# Zotino.net
KiCad netlist of a schematic drawn in Altium Designer
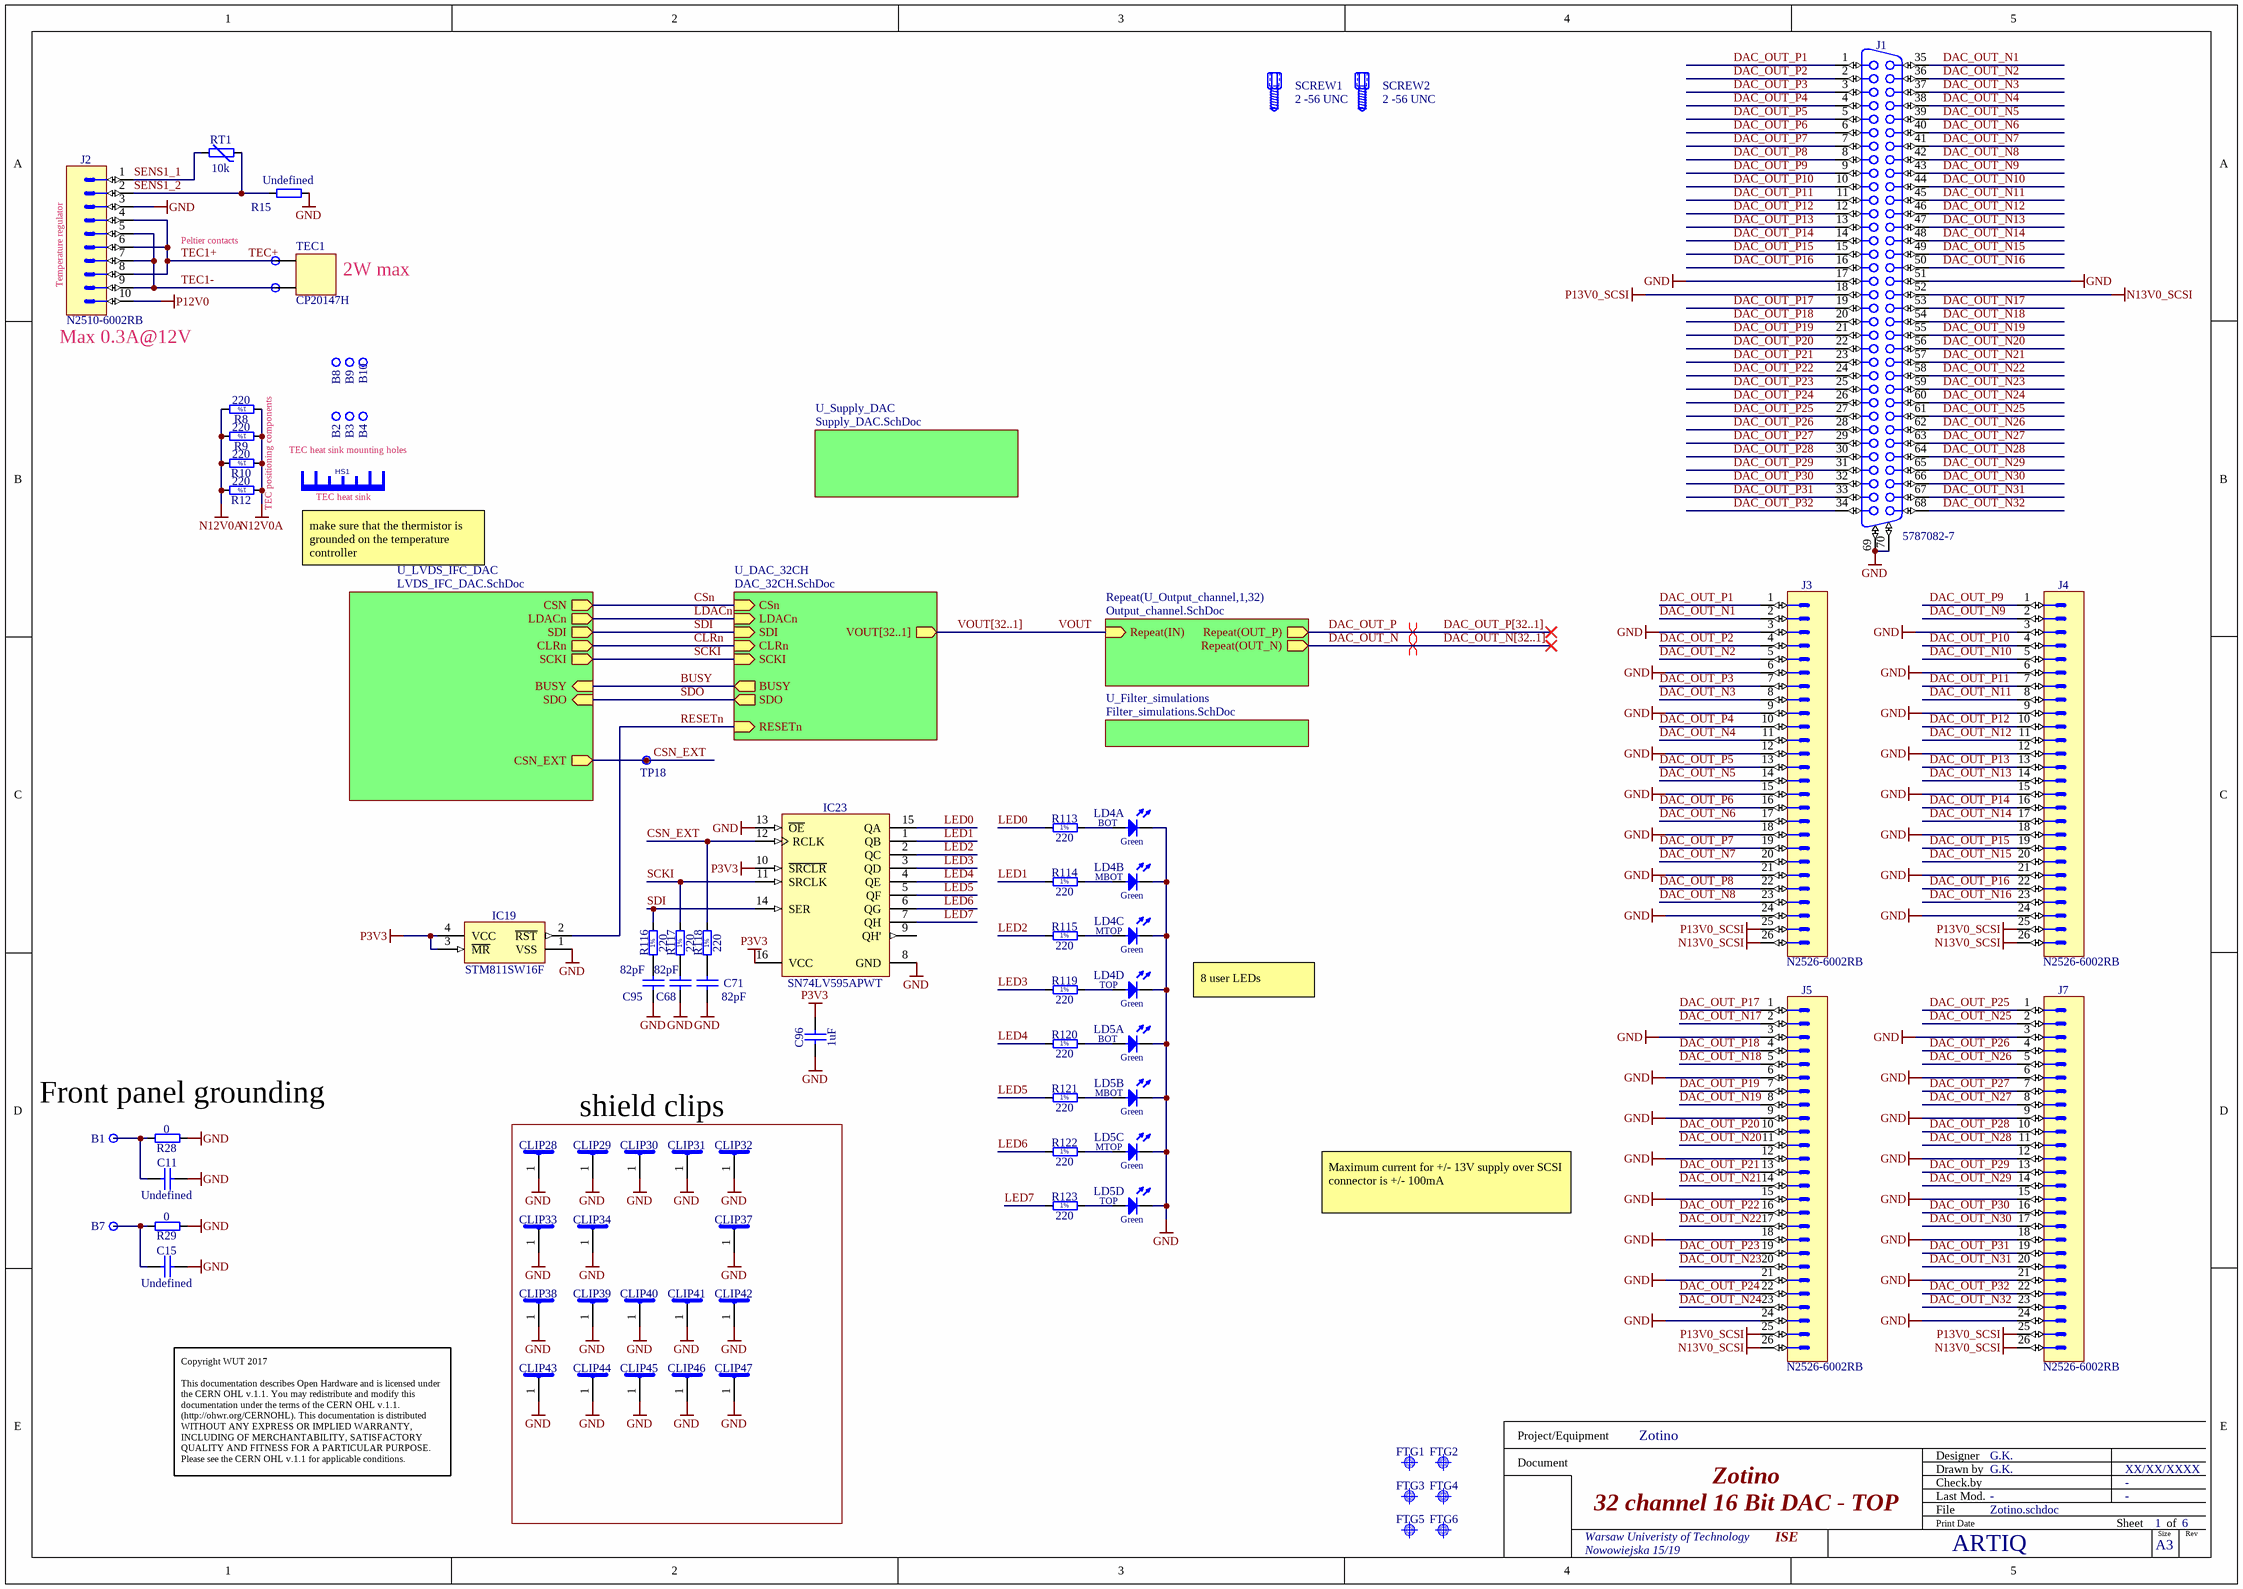
[diagram p0: Zotino.schdoc]

(export (version "E")
  (design (tool "Eeschema 10.0.6"))
  (components
    (comp (ref "B1")
      (value "Plated Hole")
      (footprint "MTG270_500")
      (description "Single Terminal Socket")
      (fields (field (name "PART NUMBER") "PLATED_HOLE2.7_PAD5.0") (field (name "AUTHOR") "CERN DEM JMW"))
      (libsource (lib "Eletro-mechanical") (part "Single Terminal Socket"))
    )
    (comp (ref "B2")
      (value "Plated Hole")
      (footprint "c130h80")
      (description "Single Terminal Socket")
      (fields (field (name "PART NUMBER") "PLATED_HOLE0.8_PAD1.3") (field (name "AUTHOR") "CERN DEM JLC"))
      (libsource (lib "Eletro-mechanical") (part "Single Terminal Socket"))
    )
    (comp (ref "B3")
      (value "Plated Hole")
      (footprint "c130h80")
      (description "Single Terminal Socket")
      (fields (field (name "PART NUMBER") "PLATED_HOLE0.8_PAD1.3") (field (name "AUTHOR") "CERN DEM JLC"))
      (libsource (lib "Eletro-mechanical") (part "Single Terminal Socket"))
    )
    (comp (ref "B4")
      (value "Plated Hole")
      (footprint "c130h80")
      (description "Single Terminal Socket")
      (fields (field (name "PART NUMBER") "PLATED_HOLE0.8_PAD1.3") (field (name "AUTHOR") "CERN DEM JLC"))
      (libsource (lib "Eletro-mechanical") (part "Single Terminal Socket"))
    )
    (comp (ref "B5")
      (value "Plated Hole")
      (footprint "c160h110")
      (description "Single Terminal Socket")
      (fields (field (name "PART NUMBER") "PLATED_HOLE1.1_PAD1.6") (field (name "AUTHOR") "CERN DEM JLC"))
      (libsource (lib "Eletro-mechanical") (part "Single Terminal Socket"))
    )
    (comp (ref "B6")
      (value "Plated Hole")
      (footprint "c160h110")
      (description "Single Terminal Socket")
      (fields (field (name "PART NUMBER") "PLATED_HOLE1.1_PAD1.6") (field (name "AUTHOR") "CERN DEM JLC"))
      (libsource (lib "Eletro-mechanical") (part "Single Terminal Socket"))
    )
    (comp (ref "B7")
      (value "Plated Hole")
      (footprint "MTG270_500")
      (description "Single Terminal Socket")
      (fields (field (name "PART NUMBER") "PLATED_HOLE2.7_PAD5.0") (field (name "AUTHOR") "CERN DEM JMW"))
      (libsource (lib "Eletro-mechanical") (part "Single Terminal Socket"))
    )
    (comp (ref "B8")
      (value "Plated Hole")
      (footprint "c130h80")
      (description "Single Terminal Socket")
      (fields (field (name "PART NUMBER") "PLATED_HOLE0.8_PAD1.3") (field (name "AUTHOR") "CERN DEM JLC"))
      (libsource (lib "Eletro-mechanical") (part "Single Terminal Socket"))
    )
    (comp (ref "B9")
      (value "Plated Hole")
      (footprint "c130h80")
      (description "Single Terminal Socket")
      (fields (field (name "PART NUMBER") "PLATED_HOLE0.8_PAD1.3") (field (name "AUTHOR") "CERN DEM JLC"))
      (libsource (lib "Eletro-mechanical") (part "Single Terminal Socket"))
    )
    (comp (ref "B10")
      (value "Plated Hole")
      (footprint "c130h80")
      (description "Single Terminal Socket")
      (fields (field (name "PART NUMBER") "PLATED_HOLE0.8_PAD1.3") (field (name "AUTHOR") "CERN DEM JLC"))
      (libsource (lib "Eletro-mechanical") (part "Single Terminal Socket"))
    )
    (comp (ref "C11")
      (value "Undefined")
      (footprint "CAPC2012X135N")
      (description "Non-polarised capacitor")
      (fields (field (name "PART NUMBER") "CC0805_NO-VALUE") (field (name "AUTHOR") "CERN DEM JLC"))
      (libsource (lib "Capacitors") (part "Capacitor - non polarized"))
    )
    (comp (ref "C15")
      (value "Undefined")
      (footprint "CAPC2012X135N")
      (description "Non-polarised capacitor")
      (fields (field (name "PART NUMBER") "CC0805_NO-VALUE") (field (name "AUTHOR") "CERN DEM JLC"))
      (libsource (lib "Capacitors") (part "Capacitor - non polarized"))
    )
    (comp (ref "C68")
      (value "82pF")
      (footprint "CAPC1608X87N")
      (description "Non-polarised capacitor")
      (fields
        (field (name "PART NUMBER") "CC0603_82PF_50V_5%_NP0")
        (field (name "VOLTAGE") "50V")
        (field (name "AUTHOR") "CERN DEM JLC")
      )
      (libsource (lib "Capacitors") (part "Capacitor - non polarized"))
    )
    (comp (ref "C71")
      (value "82pF")
      (footprint "CAPC1608X87N")
      (description "Non-polarised capacitor")
      (fields
        (field (name "PART NUMBER") "CC0603_82PF_50V_5%_NP0")
        (field (name "VOLTAGE") "50V")
        (field (name "AUTHOR") "CERN DEM JLC")
      )
      (libsource (lib "Capacitors") (part "Capacitor - non polarized"))
    )
    (comp (ref "C95")
      (value "82pF")
      (footprint "CAPC1608X87N")
      (description "Non-polarised capacitor")
      (fields
        (field (name "PART NUMBER") "CC0603_82PF_50V_5%_NP0")
        (field (name "VOLTAGE") "50V")
        (field (name "AUTHOR") "CERN DEM JLC")
      )
      (libsource (lib "Capacitors") (part "Capacitor - non polarized"))
    )
    (comp (ref "C96")
      (value "1uF")
      (footprint "CAPC1608X87N")
      (description "Non-polarised capacitor")
      (fields
        (field (name "PART NUMBER") "CC0603_1UF_25V_10%_X7R")
        (field (name "VOLTAGE") "25V")
        (field (name "AUTHOR") "CERN DEM JLC")
      )
      (libsource (lib "Capacitors") (part "Capacitor - non polarized"))
    )
    (comp (ref "CLIP28")
      (value "S1411-46R")
      (footprint "CLIP_HOLLAND-SHIELDING_LC")
      (description "Surface Mount Clip for PCB Screening Covers")
      (fields (field (name "MANUFACTURER") "HARWIN") (field (name "AUTHOR") "CERN DEM JLC"))
      (libsource (lib "LIBRARY_SCH") (part "SHIELD_CLIP"))
    )
    (comp (ref "CLIP29")
      (value "S1411-46R")
      (footprint "CLIP_HOLLAND-SHIELDING_LC")
      (description "Surface Mount Clip for PCB Screening Covers")
      (fields (field (name "MANUFACTURER") "HARWIN") (field (name "AUTHOR") "CERN DEM JLC"))
      (libsource (lib "LIBRARY_SCH") (part "SHIELD_CLIP"))
    )
    (comp (ref "CLIP30")
      (value "S1411-46R")
      (footprint "CLIP_HOLLAND-SHIELDING_LC")
      (description "Surface Mount Clip for PCB Screening Covers")
      (fields (field (name "MANUFACTURER") "HARWIN") (field (name "AUTHOR") "CERN DEM JLC"))
      (libsource (lib "LIBRARY_SCH") (part "SHIELD_CLIP"))
    )
    (comp (ref "CLIP31")
      (value "S1411-46R")
      (footprint "CLIP_HOLLAND-SHIELDING_LC")
      (description "Surface Mount Clip for PCB Screening Covers")
      (fields (field (name "MANUFACTURER") "HARWIN") (field (name "AUTHOR") "CERN DEM JLC"))
      (libsource (lib "LIBRARY_SCH") (part "SHIELD_CLIP"))
    )
    (comp (ref "CLIP32")
      (value "S1411-46R")
      (footprint "CLIP_HOLLAND-SHIELDING_LC")
      (description "Surface Mount Clip for PCB Screening Covers")
      (fields (field (name "MANUFACTURER") "HARWIN") (field (name "AUTHOR") "CERN DEM JLC"))
      (libsource (lib "LIBRARY_SCH") (part "SHIELD_CLIP"))
    )
    (comp (ref "CLIP33")
      (value "S1411-46R")
      (footprint "CLIP_HOLLAND-SHIELDING_LC")
      (description "Surface Mount Clip for PCB Screening Covers")
      (fields (field (name "MANUFACTURER") "HARWIN") (field (name "AUTHOR") "CERN DEM JLC"))
      (libsource (lib "LIBRARY_SCH") (part "SHIELD_CLIP"))
    )
    (comp (ref "CLIP34")
      (value "S1411-46R")
      (footprint "CLIP_HOLLAND-SHIELDING_LC")
      (description "Surface Mount Clip for PCB Screening Covers")
      (fields (field (name "MANUFACTURER") "HARWIN") (field (name "AUTHOR") "CERN DEM JLC"))
      (libsource (lib "LIBRARY_SCH") (part "SHIELD_CLIP"))
    )
    (comp (ref "CLIP37")
      (value "S1411-46R")
      (footprint "CLIP_HOLLAND-SHIELDING_LC")
      (description "Surface Mount Clip for PCB Screening Covers")
      (fields (field (name "MANUFACTURER") "HARWIN") (field (name "AUTHOR") "CERN DEM JLC"))
      (libsource (lib "LIBRARY_SCH") (part "SHIELD_CLIP"))
    )
    (comp (ref "CLIP38")
      (value "S1411-46R")
      (footprint "CLIP_HOLLAND-SHIELDING_LC")
      (description "Surface Mount Clip for PCB Screening Covers")
      (fields (field (name "MANUFACTURER") "HARWIN") (field (name "AUTHOR") "CERN DEM JLC"))
      (libsource (lib "LIBRARY_SCH") (part "SHIELD_CLIP"))
    )
    (comp (ref "CLIP39")
      (value "S1411-46R")
      (footprint "CLIP_HOLLAND-SHIELDING_LC")
      (description "Surface Mount Clip for PCB Screening Covers")
      (fields (field (name "MANUFACTURER") "HARWIN") (field (name "AUTHOR") "CERN DEM JLC"))
      (libsource (lib "LIBRARY_SCH") (part "SHIELD_CLIP"))
    )
    (comp (ref "CLIP40")
      (value "S1411-46R")
      (footprint "CLIP_HOLLAND-SHIELDING_LC")
      (description "Surface Mount Clip for PCB Screening Covers")
      (fields (field (name "MANUFACTURER") "HARWIN") (field (name "AUTHOR") "CERN DEM JLC"))
      (libsource (lib "LIBRARY_SCH") (part "SHIELD_CLIP"))
    )
    (comp (ref "CLIP41")
      (value "S1411-46R")
      (footprint "CLIP_HOLLAND-SHIELDING_LC")
      (description "Surface Mount Clip for PCB Screening Covers")
      (fields (field (name "MANUFACTURER") "HARWIN") (field (name "AUTHOR") "CERN DEM JLC"))
      (libsource (lib "LIBRARY_SCH") (part "SHIELD_CLIP"))
    )
    (comp (ref "CLIP42")
      (value "S1411-46R")
      (footprint "CLIP_HOLLAND-SHIELDING_LC")
      (description "Surface Mount Clip for PCB Screening Covers")
      (fields (field (name "MANUFACTURER") "HARWIN") (field (name "AUTHOR") "CERN DEM JLC"))
      (libsource (lib "LIBRARY_SCH") (part "SHIELD_CLIP"))
    )
    (comp (ref "CLIP43")
      (value "S1411-46R")
      (footprint "CLIP_HOLLAND-SHIELDING_LC")
      (description "Surface Mount Clip for PCB Screening Covers")
      (fields (field (name "MANUFACTURER") "HARWIN") (field (name "AUTHOR") "CERN DEM JLC"))
      (libsource (lib "LIBRARY_SCH") (part "SHIELD_CLIP"))
    )
    (comp (ref "CLIP44")
      (value "S1411-46R")
      (footprint "CLIP_HOLLAND-SHIELDING_LC")
      (description "Surface Mount Clip for PCB Screening Covers")
      (fields (field (name "MANUFACTURER") "HARWIN") (field (name "AUTHOR") "CERN DEM JLC"))
      (libsource (lib "LIBRARY_SCH") (part "SHIELD_CLIP"))
    )
    (comp (ref "CLIP45")
      (value "S1411-46R")
      (footprint "CLIP_HOLLAND-SHIELDING_LC")
      (description "Surface Mount Clip for PCB Screening Covers")
      (fields (field (name "MANUFACTURER") "HARWIN") (field (name "AUTHOR") "CERN DEM JLC"))
      (libsource (lib "LIBRARY_SCH") (part "SHIELD_CLIP"))
    )
    (comp (ref "CLIP46")
      (value "S1411-46R")
      (footprint "CLIP_HOLLAND-SHIELDING_LC")
      (description "Surface Mount Clip for PCB Screening Covers")
      (fields (field (name "MANUFACTURER") "HARWIN") (field (name "AUTHOR") "CERN DEM JLC"))
      (libsource (lib "LIBRARY_SCH") (part "SHIELD_CLIP"))
    )
    (comp (ref "CLIP47")
      (value "S1411-46R")
      (footprint "CLIP_HOLLAND-SHIELDING_LC")
      (description "Surface Mount Clip for PCB Screening Covers")
      (fields (field (name "MANUFACTURER") "HARWIN") (field (name "AUTHOR") "CERN DEM JLC"))
      (libsource (lib "LIBRARY_SCH") (part "SHIELD_CLIP"))
    )
    (comp (ref "FTG1")
      (value "Use only in PCB")
      (footprint "FIDUCIAL_TOP_C100-200")
      (description "Fiducial Target")
      (fields (field (name "PART NUMBER") "FIDUCIAL_TARGET_C100-200") (field (name "AUTHOR") "CERN DEM JLC"))
      (libsource (lib "Eletro-mechanical") (part "Fiducial Target"))
    )
    (comp (ref "FTG2")
      (value "Use only in PCB")
      (footprint "FIDUCIAL_TOP_C100-200")
      (description "Fiducial Target")
      (fields (field (name "PART NUMBER") "FIDUCIAL_TARGET_C100-200") (field (name "AUTHOR") "CERN DEM JLC"))
      (libsource (lib "Eletro-mechanical") (part "Fiducial Target"))
    )
    (comp (ref "FTG3")
      (value "Use only in PCB")
      (footprint "FIDUCIAL_TOP_S100-200")
      (description "Fiducial Target")
      (fields (field (name "PART NUMBER") "FIDUCIAL_TARGET_S100-200") (field (name "AUTHOR") "CERN DEM JLC"))
      (libsource (lib "Eletro-mechanical") (part "Fiducial Target"))
    )
    (comp (ref "FTG4")
      (value "Use only in PCB")
      (footprint "FIDUCIAL_TOP_S100-200")
      (description "Fiducial Target")
      (fields (field (name "PART NUMBER") "FIDUCIAL_TARGET_S100-200") (field (name "AUTHOR") "CERN DEM JLC"))
      (libsource (lib "Eletro-mechanical") (part "Fiducial Target"))
    )
    (comp (ref "FTG5")
      (value "Use only in PCB")
      (footprint "FIDUCIAL_TOP_S100-200")
      (description "Fiducial Target")
      (fields (field (name "PART NUMBER") "FIDUCIAL_TARGET_S100-200") (field (name "AUTHOR") "CERN DEM JLC"))
      (libsource (lib "Eletro-mechanical") (part "Fiducial Target"))
    )
    (comp (ref "FTG6")
      (value "Use only in PCB")
      (footprint "FIDUCIAL_TOP_S100-200")
      (description "Fiducial Target")
      (fields (field (name "PART NUMBER") "FIDUCIAL_TARGET_S100-200") (field (name "AUTHOR") "CERN DEM JLC"))
      (libsource (lib "Eletro-mechanical") (part "Fiducial Target"))
    )
    (comp (ref "HS1")
      (value "Heat Sink No Pad")
      (footprint "HSINK_ATS_ATS-56001-C3-R0")
      (description "Heat Sink Without Pad")
      (fields
        (field (name "PART NUMBER") "HSINK_ATS_ATS-56001-C3-R0")
        (field (name "MANUFACTURER") "ADVENCED THERMAL SOLUTION (ATS)")
        (field (name "AUTHOR") "GK")
      )
      (libsource (lib "LIBRARY_SCH") (part "HEAT_SINK_19x19x9"))
    )
    (comp (ref "IC19")
      (value "STM811SW16F")
      (footprint "SOT143N")
      (description "Microprocessor Reset Circuit")
      (fields (field (name "MANUFACTURER") "ST MICROELECTRONICS") (field (name "AUTHOR") "CERN DEM JLC"))
      (libsource (lib "ICs And Semiconductors") (part "STM811"))
    )
    (comp (ref "IC23")
      (value "SN74LV595APWT")
      (footprint "SOP65P640X120-16N")
      (description "8-Bit Shift Register With 3-State Output Register")
      (fields (field (name "MANUFACTURER") "TEXAS INSTRUMENTS") (field (name "AUTHOR") "CERN DEM JLC"))
      (libsource (lib "ICs And Semiconductors") (part "74595"))
    )
    (comp (ref "J1")
      (value "D-SUB")
      (footprint "TYCO_5787082-7")
      (description "68 contacts, AMPLIMITE .050\", Right Angled Receptacle Series III")
      (fields
        (field (name "PART NUMBER") "TYCO_5787082-7")
        (field (name "MANUFACTURER") "TYCO ELECTRONICS")
        (field (name "MANUFACTURER PART NUMBER") "5787082-7")
        (field (name "AUTHOR") "CERN DEM JLC")
      )
      (libsource (lib "Connectors") (part "TYCO_5787082-7"))
    )
    (comp (ref "J2")
      (value "Header 10")
      (footprint "3M_N2510-6002RB")
      (description "Connector 10 Male")
      (fields
        (field (name "PART NUMBER") "3M_N2510-6002RB")
        (field (name "MANUFACTURER") "3M")
        (field (name "MANUFACTURER PART NUMBER") "N2510-6002RB")
        (field (name "AUTHOR") "CERN DEM JLC")
      )
      (libsource (lib "Connectors") (part "Connector 10 Male"))
    )
    (comp (ref "J3")
      (value "Header 26")
      (footprint "3M_N2526-6002RB")
      (description "Connector 26 Male")
      (fields
        (field (name "PART NUMBER") "3M_N2526-6002RB")
        (field (name "MANUFACTURER") "3M")
        (field (name "MANUFACTURER PART NUMBER") "N2526-6002RB")
        (field (name "AUTHOR") "CERN DEM JLC")
      )
      (libsource (lib "Connectors") (part "Connector 26 Male"))
    )
    (comp (ref "J4")
      (value "Header 26")
      (footprint "3M_N2526-6002RB")
      (description "Connector 26 Male")
      (fields
        (field (name "PART NUMBER") "3M_N2526-6002RB")
        (field (name "MANUFACTURER") "3M")
        (field (name "MANUFACTURER PART NUMBER") "N2526-6002RB")
        (field (name "AUTHOR") "CERN DEM JLC")
      )
      (libsource (lib "Connectors") (part "Connector 26 Male"))
    )
    (comp (ref "J5")
      (value "Header 26")
      (footprint "3M_N2526-6002RB")
      (description "Connector 26 Male")
      (fields
        (field (name "PART NUMBER") "3M_N2526-6002RB")
        (field (name "MANUFACTURER") "3M")
        (field (name "MANUFACTURER PART NUMBER") "N2526-6002RB")
        (field (name "AUTHOR") "CERN DEM JLC")
      )
      (libsource (lib "Connectors") (part "Connector 26 Male"))
    )
    (comp (ref "J7")
      (value "Header 26")
      (footprint "3M_N2526-6002RB")
      (description "Connector 26 Male")
      (fields
        (field (name "PART NUMBER") "3M_N2526-6002RB")
        (field (name "MANUFACTURER") "3M")
        (field (name "MANUFACTURER PART NUMBER") "N2526-6002RB")
        (field (name "AUTHOR") "CERN DEM JLC")
      )
      (libsource (lib "Connectors") (part "Connector 26 Male"))
    )
    (comp (ref "LD4")
      (value "Green")
      (footprint "LED_BIVAR_H485CGDL")
      (description "LED x4 Green 1C2A-BOT_3C4A_5C6A_7C8A-TOP")
      (fields
        (field (name "PART NUMBER") "LED_BIVAR_H485CGDL")
        (field (name "MANUFACTURER") "BIVAR")
        (field (name "AUTHOR") "CERN DEM JLC")
      )
      (libsource (lib "ICs And Semiconductors") (part "LED x4 Green 1C2A-BOT_3C4A_5C6A_7C8A-TOP"))
    )
    (comp (ref "LD5")
      (value "Green")
      (footprint "LED_BIVAR_H485CGDL")
      (description "LED x4 Green 1C2A-BOT_3C4A_5C6A_7C8A-TOP")
      (fields
        (field (name "PART NUMBER") "LED_BIVAR_H485CGDL")
        (field (name "MANUFACTURER") "BIVAR")
        (field (name "AUTHOR") "CERN DEM JLC")
      )
      (libsource (lib "ICs And Semiconductors") (part "LED x4 Green 1C2A-BOT_3C4A_5C6A_7C8A-TOP"))
    )
    (comp (ref "R8")
      (value "220")
      (footprint "RESC1608X55N")
      (description "Resistor - 1%")
      (fields
        (field (name "PART NUMBER") "R0603_220R_1%_0.1W_100PPM")
        (field (name "POWER") "0.1W")
        (field (name "AUTHOR") "CERN DEM JLC")
      )
      (libsource (lib "Resistors") (part "Resistor - 1%"))
    )
    (comp (ref "R9")
      (value "220")
      (footprint "RESC1608X55N")
      (description "Resistor - 1%")
      (fields
        (field (name "PART NUMBER") "R0603_220R_1%_0.1W_100PPM")
        (field (name "POWER") "0.1W")
        (field (name "AUTHOR") "CERN DEM JLC")
      )
      (libsource (lib "Resistors") (part "Resistor - 1%"))
    )
    (comp (ref "R10")
      (value "220")
      (footprint "RESC1608X55N")
      (description "Resistor - 1%")
      (fields
        (field (name "PART NUMBER") "R0603_220R_1%_0.1W_100PPM")
        (field (name "POWER") "0.1W")
        (field (name "AUTHOR") "CERN DEM JLC")
      )
      (libsource (lib "Resistors") (part "Resistor - 1%"))
    )
    (comp (ref "R12")
      (value "220")
      (footprint "RESC1608X55N")
      (description "Resistor - 1%")
      (fields
        (field (name "PART NUMBER") "R0603_220R_1%_0.1W_100PPM")
        (field (name "POWER") "0.1W")
        (field (name "AUTHOR") "CERN DEM JLC")
      )
      (libsource (lib "Resistors") (part "Resistor - 1%"))
    )
    (comp (ref "R15")
      (value "Undefined")
      (footprint "RESC1608X55N")
      (description "Resistor")
      (fields (field (name "PART NUMBER") "R0603_NO-VALUE") (field (name "AUTHOR") "CERN DEM JLC"))
      (libsource (lib "Resistors") (part "Resistor"))
    )
    (comp (ref "R28")
      (value "0")
      (footprint "RESC1608X55N")
      (description "Resistor")
      (fields
        (field (name "PART NUMBER") "R0603_0R_JUMPER")
        (field (name "MANUFACTURER") "GENERIC")
        (field (name "AUTHOR") "CERN DEM JLC")
      )
      (libsource (lib "Resistors") (part "Resistor"))
    )
    (comp (ref "R29")
      (value "0")
      (footprint "RESC1608X55N")
      (description "Resistor")
      (fields
        (field (name "PART NUMBER") "R0603_0R_JUMPER")
        (field (name "MANUFACTURER") "GENERIC")
        (field (name "AUTHOR") "CERN DEM JLC")
      )
      (libsource (lib "Resistors") (part "Resistor"))
    )
    (comp (ref "R113")
      (value "220")
      (footprint "RESC1608X55N")
      (description "Resistor - 1%")
      (fields
        (field (name "PART NUMBER") "R0603_220R_1%_0.1W_100PPM")
        (field (name "POWER") "0.1W")
        (field (name "AUTHOR") "CERN DEM JLC")
      )
      (libsource (lib "Resistors") (part "Resistor - 1%"))
    )
    (comp (ref "R114")
      (value "220")
      (footprint "RESC1608X55N")
      (description "Resistor - 1%")
      (fields
        (field (name "PART NUMBER") "R0603_220R_1%_0.1W_100PPM")
        (field (name "POWER") "0.1W")
        (field (name "AUTHOR") "CERN DEM JLC")
      )
      (libsource (lib "Resistors") (part "Resistor - 1%"))
    )
    (comp (ref "R115")
      (value "220")
      (footprint "RESC1608X55N")
      (description "Resistor - 1%")
      (fields
        (field (name "PART NUMBER") "R0603_220R_1%_0.1W_100PPM")
        (field (name "POWER") "0.1W")
        (field (name "AUTHOR") "CERN DEM JLC")
      )
      (libsource (lib "Resistors") (part "Resistor - 1%"))
    )
    (comp (ref "R116")
      (value "220")
      (footprint "RESC1608X55N")
      (description "Resistor - 1%")
      (fields
        (field (name "PART NUMBER") "R0603_220R_1%_0.1W_100PPM")
        (field (name "POWER") "0.1W")
        (field (name "AUTHOR") "CERN DEM JLC")
      )
      (libsource (lib "Resistors") (part "Resistor - 1%"))
    )
    (comp (ref "R117")
      (value "220")
      (footprint "RESC1608X55N")
      (description "Resistor - 1%")
      (fields
        (field (name "PART NUMBER") "R0603_220R_1%_0.1W_100PPM")
        (field (name "POWER") "0.1W")
        (field (name "AUTHOR") "CERN DEM JLC")
      )
      (libsource (lib "Resistors") (part "Resistor - 1%"))
    )
    (comp (ref "R118")
      (value "220")
      (footprint "RESC1608X55N")
      (description "Resistor - 1%")
      (fields
        (field (name "PART NUMBER") "R0603_220R_1%_0.1W_100PPM")
        (field (name "POWER") "0.1W")
        (field (name "AUTHOR") "CERN DEM JLC")
      )
      (libsource (lib "Resistors") (part "Resistor - 1%"))
    )
    (comp (ref "R119")
      (value "220")
      (footprint "RESC1608X55N")
      (description "Resistor - 1%")
      (fields
        (field (name "PART NUMBER") "R0603_220R_1%_0.1W_100PPM")
        (field (name "POWER") "0.1W")
        (field (name "AUTHOR") "CERN DEM JLC")
      )
      (libsource (lib "Resistors") (part "Resistor - 1%"))
    )
    (comp (ref "R120")
      (value "220")
      (footprint "RESC1608X55N")
      (description "Resistor - 1%")
      (fields
        (field (name "PART NUMBER") "R0603_220R_1%_0.1W_100PPM")
        (field (name "POWER") "0.1W")
        (field (name "AUTHOR") "CERN DEM JLC")
      )
      (libsource (lib "Resistors") (part "Resistor - 1%"))
    )
    (comp (ref "R121")
      (value "220")
      (footprint "RESC1608X55N")
      (description "Resistor - 1%")
      (fields
        (field (name "PART NUMBER") "R0603_220R_1%_0.1W_100PPM")
        (field (name "POWER") "0.1W")
        (field (name "AUTHOR") "CERN DEM JLC")
      )
      (libsource (lib "Resistors") (part "Resistor - 1%"))
    )
    (comp (ref "R122")
      (value "220")
      (footprint "RESC1608X55N")
      (description "Resistor - 1%")
      (fields
        (field (name "PART NUMBER") "R0603_220R_1%_0.1W_100PPM")
        (field (name "POWER") "0.1W")
        (field (name "AUTHOR") "CERN DEM JLC")
      )
      (libsource (lib "Resistors") (part "Resistor - 1%"))
    )
    (comp (ref "R123")
      (value "220")
      (footprint "RESC1608X55N")
      (description "Resistor - 1%")
      (fields
        (field (name "PART NUMBER") "R0603_220R_1%_0.1W_100PPM")
        (field (name "POWER") "0.1W")
        (field (name "AUTHOR") "CERN DEM JLC")
      )
      (libsource (lib "Resistors") (part "Resistor - 1%"))
    )
    (comp (ref "RT1")
      (value "10k")
      (footprint "THERMC1608X90N")
      (description "Thermistor NTC (Negative Temperature Coefficient)")
      (fields
        (field (name "PART NUMBER") "THERM_NTC_10K_EPCOS_B57330V2103J260")
        (field (name "POWER") "180mW")
        (field (name "AUTHOR") "CERN DEM BC")
      )
      (libsource (lib "Resistors") (part "Thermistor NTC"))
    )
    (comp (ref "SCREW1")
      (value "2 -56 UNC")
      (footprint "TYCO_786585-2")
      (description "SCSI Screw Lock")
      (fields
        (field (name "PART NUMBER") "TYCO_786585-2")
        (field (name "MANUFACTURER") "TYCO ELECTRONICS")
        (field (name "AUTHOR") "GK")
      )
      (libsource (lib "LIBRARY_SCH") (part "MECH_Tyco_SCSI_Screwlock"))
    )
    (comp (ref "SCREW2")
      (value "2 -56 UNC")
      (footprint "TYCO_786585-2")
      (description "SCSI Screw Lock")
      (fields
        (field (name "PART NUMBER") "TYCO_786585-2")
        (field (name "MANUFACTURER") "TYCO ELECTRONICS")
        (field (name "AUTHOR") "GK")
      )
      (libsource (lib "LIBRARY_SCH") (part "MECH_Tyco_SCSI_Screwlock"))
    )
    (comp (ref "TEC1")
      (value "CP20147H")
      (footprint "TEC_CP20147H")
      (description "Peltier Module 15x15 mm")
      (libsource (lib "LIBRARY_SCH") (part "TEC_CP20147H"))
    )
    (comp (ref "TP18")
      (value "Test Point")
      (footprint "TPS127")
      (fields (field (name "PART NUMBER") "SMD_PAD_1.27X1.27MM") (field (name "AUTHOR") "CERN DEM JLC"))
      (libsource (lib "Eletro-mechanical") (part "Test Point"))
    )
  )
  (nets
    (net (code "35") (name "/CSN_EXT") (class "Default")
      (node (ref "IC23") (pin "12") (pinfunction "RCLK_12") (pintype "input"))
      (node (ref "R118") (pin "2") (pinfunction "2_2") (pintype "passive"))
      (node (ref "TP18") (pin "1") (pinfunction "1_1") (pintype "bidirectional"))
    )
    (net (code "38") (name "/DAC_OUT_N1") (class "Default")
      (node (ref "J1") (pin "35") (pinfunction "35_35") (pintype "bidirectional"))
      (node (ref "J3") (pin "2") (pinfunction "2_2") (pintype "bidirectional"))
    )
    (net (code "39") (name "/DAC_OUT_N2") (class "Default")
      (node (ref "J1") (pin "36") (pinfunction "36_36") (pintype "bidirectional"))
      (node (ref "J3") (pin "5") (pinfunction "5_5") (pintype "bidirectional"))
    )
    (net (code "40") (name "/DAC_OUT_N3") (class "Default")
      (node (ref "J1") (pin "37") (pinfunction "37_37") (pintype "bidirectional"))
      (node (ref "J3") (pin "8") (pinfunction "8_8") (pintype "bidirectional"))
    )
    (net (code "41") (name "/DAC_OUT_N4") (class "Default")
      (node (ref "J1") (pin "38") (pinfunction "38_38") (pintype "bidirectional"))
      (node (ref "J3") (pin "11") (pinfunction "11_11") (pintype "bidirectional"))
    )
    (net (code "42") (name "/DAC_OUT_N5") (class "Default")
      (node (ref "J1") (pin "39") (pinfunction "39_39") (pintype "bidirectional"))
      (node (ref "J3") (pin "14") (pinfunction "14_14") (pintype "bidirectional"))
    )
    (net (code "43") (name "/DAC_OUT_N6") (class "Default")
      (node (ref "J1") (pin "40") (pinfunction "40_40") (pintype "bidirectional"))
      (node (ref "J3") (pin "17") (pinfunction "17_17") (pintype "bidirectional"))
    )
    (net (code "44") (name "/DAC_OUT_N7") (class "Default")
      (node (ref "J1") (pin "41") (pinfunction "41_41") (pintype "bidirectional"))
      (node (ref "J3") (pin "20") (pinfunction "20_20") (pintype "bidirectional"))
    )
    (net (code "45") (name "/DAC_OUT_N8") (class "Default")
      (node (ref "J1") (pin "42") (pinfunction "42_42") (pintype "bidirectional"))
      (node (ref "J3") (pin "23") (pinfunction "23_23") (pintype "bidirectional"))
    )
    (net (code "46") (name "/DAC_OUT_N9") (class "Default")
      (node (ref "J1") (pin "43") (pinfunction "43_43") (pintype "bidirectional"))
      (node (ref "J4") (pin "2") (pinfunction "2_2") (pintype "bidirectional"))
    )
    (net (code "47") (name "/DAC_OUT_N10") (class "Default")
      (node (ref "J1") (pin "44") (pinfunction "44_44") (pintype "bidirectional"))
      (node (ref "J4") (pin "5") (pinfunction "5_5") (pintype "bidirectional"))
    )
    (net (code "48") (name "/DAC_OUT_N11") (class "Default")
      (node (ref "J1") (pin "45") (pinfunction "45_45") (pintype "bidirectional"))
      (node (ref "J4") (pin "8") (pinfunction "8_8") (pintype "bidirectional"))
    )
    (net (code "49") (name "/DAC_OUT_N12") (class "Default")
      (node (ref "J1") (pin "46") (pinfunction "46_46") (pintype "bidirectional"))
      (node (ref "J4") (pin "11") (pinfunction "11_11") (pintype "bidirectional"))
    )
    (net (code "50") (name "/DAC_OUT_N13") (class "Default")
      (node (ref "J1") (pin "47") (pinfunction "47_47") (pintype "bidirectional"))
      (node (ref "J4") (pin "14") (pinfunction "14_14") (pintype "bidirectional"))
    )
    (net (code "51") (name "/DAC_OUT_N14") (class "Default")
      (node (ref "J1") (pin "48") (pinfunction "48_48") (pintype "bidirectional"))
      (node (ref "J4") (pin "17") (pinfunction "17_17") (pintype "bidirectional"))
    )
    (net (code "52") (name "/DAC_OUT_N15") (class "Default")
      (node (ref "J1") (pin "49") (pinfunction "49_49") (pintype "bidirectional"))
      (node (ref "J4") (pin "20") (pinfunction "20_20") (pintype "bidirectional"))
    )
    (net (code "53") (name "/DAC_OUT_N16") (class "Default")
      (node (ref "J1") (pin "50") (pinfunction "50_50") (pintype "bidirectional"))
      (node (ref "J4") (pin "23") (pinfunction "23_23") (pintype "bidirectional"))
    )
    (net (code "54") (name "/DAC_OUT_N17") (class "Default")
      (node (ref "J1") (pin "53") (pinfunction "53_53") (pintype "bidirectional"))
      (node (ref "J5") (pin "2") (pinfunction "2_2") (pintype "bidirectional"))
    )
    (net (code "55") (name "/DAC_OUT_N18") (class "Default")
      (node (ref "J1") (pin "54") (pinfunction "54_54") (pintype "bidirectional"))
      (node (ref "J5") (pin "5") (pinfunction "5_5") (pintype "bidirectional"))
    )
    (net (code "56") (name "/DAC_OUT_N19") (class "Default")
      (node (ref "J1") (pin "55") (pinfunction "55_55") (pintype "bidirectional"))
      (node (ref "J5") (pin "8") (pinfunction "8_8") (pintype "bidirectional"))
    )
    (net (code "57") (name "/DAC_OUT_N20") (class "Default")
      (node (ref "J1") (pin "56") (pinfunction "56_56") (pintype "bidirectional"))
      (node (ref "J5") (pin "11") (pinfunction "11_11") (pintype "bidirectional"))
    )
    (net (code "58") (name "/DAC_OUT_N21") (class "Default")
      (node (ref "J1") (pin "57") (pinfunction "57_57") (pintype "bidirectional"))
      (node (ref "J5") (pin "14") (pinfunction "14_14") (pintype "bidirectional"))
    )
    (net (code "59") (name "/DAC_OUT_N22") (class "Default")
      (node (ref "J1") (pin "58") (pinfunction "58_58") (pintype "bidirectional"))
      (node (ref "J5") (pin "17") (pinfunction "17_17") (pintype "bidirectional"))
    )
    (net (code "60") (name "/DAC_OUT_N23") (class "Default")
      (node (ref "J1") (pin "59") (pinfunction "59_59") (pintype "bidirectional"))
      (node (ref "J5") (pin "20") (pinfunction "20_20") (pintype "bidirectional"))
    )
    (net (code "61") (name "/DAC_OUT_N24") (class "Default")
      (node (ref "J1") (pin "60") (pinfunction "60_60") (pintype "bidirectional"))
      (node (ref "J5") (pin "23") (pinfunction "23_23") (pintype "bidirectional"))
    )
    (net (code "62") (name "/DAC_OUT_N25") (class "Default")
      (node (ref "J1") (pin "61") (pinfunction "61_61") (pintype "bidirectional"))
      (node (ref "J7") (pin "2") (pinfunction "2_2") (pintype "bidirectional"))
    )
    (net (code "63") (name "/DAC_OUT_N26") (class "Default")
      (node (ref "J1") (pin "62") (pinfunction "62_62") (pintype "bidirectional"))
      (node (ref "J7") (pin "5") (pinfunction "5_5") (pintype "bidirectional"))
    )
    (net (code "64") (name "/DAC_OUT_N27") (class "Default")
      (node (ref "J1") (pin "63") (pinfunction "63_63") (pintype "bidirectional"))
      (node (ref "J7") (pin "8") (pinfunction "8_8") (pintype "bidirectional"))
    )
    (net (code "65") (name "/DAC_OUT_N28") (class "Default")
      (node (ref "J1") (pin "64") (pinfunction "64_64") (pintype "bidirectional"))
      (node (ref "J7") (pin "11") (pinfunction "11_11") (pintype "bidirectional"))
    )
    (net (code "66") (name "/DAC_OUT_N29") (class "Default")
      (node (ref "J1") (pin "65") (pinfunction "65_65") (pintype "bidirectional"))
      (node (ref "J7") (pin "14") (pinfunction "14_14") (pintype "bidirectional"))
    )
    (net (code "67") (name "/DAC_OUT_N30") (class "Default")
      (node (ref "J1") (pin "66") (pinfunction "66_66") (pintype "bidirectional"))
      (node (ref "J7") (pin "17") (pinfunction "17_17") (pintype "bidirectional"))
    )
    (net (code "68") (name "/DAC_OUT_N31") (class "Default")
      (node (ref "J1") (pin "67") (pinfunction "67_67") (pintype "bidirectional"))
      (node (ref "J7") (pin "20") (pinfunction "20_20") (pintype "bidirectional"))
    )
    (net (code "69") (name "/DAC_OUT_N32") (class "Default")
      (node (ref "J1") (pin "68") (pinfunction "68_68") (pintype "bidirectional"))
      (node (ref "J7") (pin "23") (pinfunction "23_23") (pintype "bidirectional"))
    )
    (net (code "72") (name "/DAC_OUT_P1") (class "Default")
      (node (ref "J1") (pin "1") (pinfunction "1_1") (pintype "bidirectional"))
      (node (ref "J3") (pin "1") (pinfunction "1_1") (pintype "bidirectional"))
    )
    (net (code "73") (name "/DAC_OUT_P2") (class "Default")
      (node (ref "J1") (pin "2") (pinfunction "2_2") (pintype "bidirectional"))
      (node (ref "J3") (pin "4") (pinfunction "4_4") (pintype "bidirectional"))
    )
    (net (code "74") (name "/DAC_OUT_P3") (class "Default")
      (node (ref "J1") (pin "3") (pinfunction "3_3") (pintype "bidirectional"))
      (node (ref "J3") (pin "7") (pinfunction "7_7") (pintype "bidirectional"))
    )
    (net (code "75") (name "/DAC_OUT_P4") (class "Default")
      (node (ref "J1") (pin "4") (pinfunction "4_4") (pintype "bidirectional"))
      (node (ref "J3") (pin "10") (pinfunction "10_10") (pintype "bidirectional"))
    )
    (net (code "76") (name "/DAC_OUT_P5") (class "Default")
      (node (ref "J1") (pin "5") (pinfunction "5_5") (pintype "bidirectional"))
      (node (ref "J3") (pin "13") (pinfunction "13_13") (pintype "bidirectional"))
    )
    (net (code "77") (name "/DAC_OUT_P6") (class "Default")
      (node (ref "J1") (pin "6") (pinfunction "6_6") (pintype "bidirectional"))
      (node (ref "J3") (pin "16") (pinfunction "16_16") (pintype "bidirectional"))
    )
    (net (code "78") (name "/DAC_OUT_P7") (class "Default")
      (node (ref "J1") (pin "7") (pinfunction "7_7") (pintype "bidirectional"))
      (node (ref "J3") (pin "19") (pinfunction "19_19") (pintype "bidirectional"))
    )
    (net (code "79") (name "/DAC_OUT_P8") (class "Default")
      (node (ref "J1") (pin "8") (pinfunction "8_8") (pintype "bidirectional"))
      (node (ref "J3") (pin "22") (pinfunction "22_22") (pintype "bidirectional"))
    )
    (net (code "80") (name "/DAC_OUT_P9") (class "Default")
      (node (ref "J1") (pin "9") (pinfunction "9_9") (pintype "bidirectional"))
      (node (ref "J4") (pin "1") (pinfunction "1_1") (pintype "bidirectional"))
    )
    (net (code "81") (name "/DAC_OUT_P10") (class "Default")
      (node (ref "J1") (pin "10") (pinfunction "10_10") (pintype "bidirectional"))
      (node (ref "J4") (pin "4") (pinfunction "4_4") (pintype "bidirectional"))
    )
    (net (code "82") (name "/DAC_OUT_P11") (class "Default")
      (node (ref "J1") (pin "11") (pinfunction "11_11") (pintype "bidirectional"))
      (node (ref "J4") (pin "7") (pinfunction "7_7") (pintype "bidirectional"))
    )
    (net (code "83") (name "/DAC_OUT_P12") (class "Default")
      (node (ref "J1") (pin "12") (pinfunction "12_12") (pintype "bidirectional"))
      (node (ref "J4") (pin "10") (pinfunction "10_10") (pintype "bidirectional"))
    )
    (net (code "84") (name "/DAC_OUT_P13") (class "Default")
      (node (ref "J1") (pin "13") (pinfunction "13_13") (pintype "bidirectional"))
      (node (ref "J4") (pin "13") (pinfunction "13_13") (pintype "bidirectional"))
    )
    (net (code "85") (name "/DAC_OUT_P14") (class "Default")
      (node (ref "J1") (pin "14") (pinfunction "14_14") (pintype "bidirectional"))
      (node (ref "J4") (pin "16") (pinfunction "16_16") (pintype "bidirectional"))
    )
    (net (code "86") (name "/DAC_OUT_P15") (class "Default")
      (node (ref "J1") (pin "15") (pinfunction "15_15") (pintype "bidirectional"))
      (node (ref "J4") (pin "19") (pinfunction "19_19") (pintype "bidirectional"))
    )
    (net (code "87") (name "/DAC_OUT_P16") (class "Default")
      (node (ref "J1") (pin "16") (pinfunction "16_16") (pintype "bidirectional"))
      (node (ref "J4") (pin "22") (pinfunction "22_22") (pintype "bidirectional"))
    )
    (net (code "88") (name "/DAC_OUT_P17") (class "Default")
      (node (ref "J1") (pin "19") (pinfunction "19_19") (pintype "bidirectional"))
      (node (ref "J5") (pin "1") (pinfunction "1_1") (pintype "bidirectional"))
    )
    (net (code "89") (name "/DAC_OUT_P18") (class "Default")
      (node (ref "J1") (pin "20") (pinfunction "20_20") (pintype "bidirectional"))
      (node (ref "J5") (pin "4") (pinfunction "4_4") (pintype "bidirectional"))
    )
    (net (code "90") (name "/DAC_OUT_P19") (class "Default")
      (node (ref "J1") (pin "21") (pinfunction "21_21") (pintype "bidirectional"))
      (node (ref "J5") (pin "7") (pinfunction "7_7") (pintype "bidirectional"))
    )
    (net (code "91") (name "/DAC_OUT_P20") (class "Default")
      (node (ref "J1") (pin "22") (pinfunction "22_22") (pintype "bidirectional"))
      (node (ref "J5") (pin "10") (pinfunction "10_10") (pintype "bidirectional"))
    )
    (net (code "92") (name "/DAC_OUT_P21") (class "Default")
      (node (ref "J1") (pin "23") (pinfunction "23_23") (pintype "bidirectional"))
      (node (ref "J5") (pin "13") (pinfunction "13_13") (pintype "bidirectional"))
    )
    (net (code "93") (name "/DAC_OUT_P22") (class "Default")
      (node (ref "J1") (pin "24") (pinfunction "24_24") (pintype "bidirectional"))
      (node (ref "J5") (pin "16") (pinfunction "16_16") (pintype "bidirectional"))
    )
    (net (code "94") (name "/DAC_OUT_P23") (class "Default")
      (node (ref "J1") (pin "25") (pinfunction "25_25") (pintype "bidirectional"))
      (node (ref "J5") (pin "19") (pinfunction "19_19") (pintype "bidirectional"))
    )
    (net (code "95") (name "/DAC_OUT_P24") (class "Default")
      (node (ref "J1") (pin "26") (pinfunction "26_26") (pintype "bidirectional"))
      (node (ref "J5") (pin "22") (pinfunction "22_22") (pintype "bidirectional"))
    )
    (net (code "96") (name "/DAC_OUT_P25") (class "Default")
      (node (ref "J1") (pin "27") (pinfunction "27_27") (pintype "bidirectional"))
      (node (ref "J7") (pin "1") (pinfunction "1_1") (pintype "bidirectional"))
    )
    (net (code "97") (name "/DAC_OUT_P26") (class "Default")
      (node (ref "J1") (pin "28") (pinfunction "28_28") (pintype "bidirectional"))
      (node (ref "J7") (pin "4") (pinfunction "4_4") (pintype "bidirectional"))
    )
    (net (code "98") (name "/DAC_OUT_P27") (class "Default")
      (node (ref "J1") (pin "29") (pinfunction "29_29") (pintype "bidirectional"))
      (node (ref "J7") (pin "7") (pinfunction "7_7") (pintype "bidirectional"))
    )
    (net (code "99") (name "/DAC_OUT_P28") (class "Default")
      (node (ref "J1") (pin "30") (pinfunction "30_30") (pintype "bidirectional"))
      (node (ref "J7") (pin "10") (pinfunction "10_10") (pintype "bidirectional"))
    )
    (net (code "100") (name "/DAC_OUT_P29") (class "Default")
      (node (ref "J1") (pin "31") (pinfunction "31_31") (pintype "bidirectional"))
      (node (ref "J7") (pin "13") (pinfunction "13_13") (pintype "bidirectional"))
    )
    (net (code "101") (name "/DAC_OUT_P30") (class "Default")
      (node (ref "J1") (pin "32") (pinfunction "32_32") (pintype "bidirectional"))
      (node (ref "J7") (pin "16") (pinfunction "16_16") (pintype "bidirectional"))
    )
    (net (code "102") (name "/DAC_OUT_P31") (class "Default")
      (node (ref "J1") (pin "33") (pinfunction "33_33") (pintype "bidirectional"))
      (node (ref "J7") (pin "19") (pinfunction "19_19") (pintype "bidirectional"))
    )
    (net (code "103") (name "/DAC_OUT_P32") (class "Default")
      (node (ref "J1") (pin "34") (pinfunction "34_34") (pintype "bidirectional"))
      (node (ref "J7") (pin "22") (pinfunction "22_22") (pintype "bidirectional"))
    )
    (net (code "106") (name "/LED0") (class "Default")
      (node (ref "IC23") (pin "15") (pinfunction "QA_15") (pintype "tri_state"))
      (node (ref "R113") (pin "1") (pinfunction "1_1") (pintype "passive"))
    )
    (net (code "107") (name "/LED1") (class "Default")
      (node (ref "IC23") (pin "1") (pinfunction "QB_1") (pintype "tri_state"))
      (node (ref "R114") (pin "1") (pinfunction "1_1") (pintype "passive"))
    )
    (net (code "108") (name "/LED2") (class "Default")
      (node (ref "IC23") (pin "2") (pinfunction "QC_2") (pintype "tri_state"))
      (node (ref "R115") (pin "1") (pinfunction "1_1") (pintype "passive"))
    )
    (net (code "109") (name "/LED3") (class "Default")
      (node (ref "IC23") (pin "3") (pinfunction "QD_3") (pintype "tri_state"))
      (node (ref "R119") (pin "1") (pinfunction "1_1") (pintype "passive"))
    )
    (net (code "110") (name "/LED4") (class "Default")
      (node (ref "IC23") (pin "4") (pinfunction "QE_4") (pintype "tri_state"))
      (node (ref "R120") (pin "1") (pinfunction "1_1") (pintype "passive"))
    )
    (net (code "111") (name "/LED5") (class "Default")
      (node (ref "IC23") (pin "5") (pinfunction "QF_5") (pintype "tri_state"))
      (node (ref "R121") (pin "1") (pinfunction "1_1") (pintype "passive"))
    )
    (net (code "112") (name "/LED6") (class "Default")
      (node (ref "IC23") (pin "6") (pinfunction "QG_6") (pintype "tri_state"))
      (node (ref "R122") (pin "1") (pinfunction "1_1") (pintype "passive"))
    )
    (net (code "113") (name "/LED7") (class "Default")
      (node (ref "IC23") (pin "7") (pinfunction "QH_7") (pintype "tri_state"))
      (node (ref "R123") (pin "1") (pinfunction "1_1") (pintype "passive"))
    )
    (net (code "114") (name "/RESETn") (class "Default")
      (node (ref "IC19") (pin "2") (pinfunction "~{RST}_2") (pintype "output"))
    )
    (net (code "115") (name "/SCKI") (class "Default")
      (node (ref "IC23") (pin "11") (pinfunction "SRCLK_11") (pintype "input"))
      (node (ref "R117") (pin "2") (pinfunction "2_2") (pintype "passive"))
    )
    (net (code "116") (name "/SDI") (class "Default")
      (node (ref "IC23") (pin "14") (pinfunction "SER_14") (pintype "input"))
      (node (ref "R116") (pin "2") (pinfunction "2_2") (pintype "passive"))
    )
    (net (code "118") (name "/SENS1_1") (class "Default")
      (node (ref "J2") (pin "1") (pinfunction "1_1") (pintype "bidirectional"))
      (node (ref "RT1") (pin "1") (pinfunction "1_1") (pintype "passive"))
    )
    (net (code "119") (name "/SENS1_2") (class "Default")
      (node (ref "J2") (pin "2") (pinfunction "2_2") (pintype "bidirectional"))
      (node (ref "R15") (pin "2") (pinfunction "2_2") (pintype "passive"))
      (node (ref "RT1") (pin "2") (pinfunction "2_2") (pintype "passive"))
    )
    (net (code "120") (name "/TEC+") (class "Default")
      (node (ref "B5") (pin "1") (pinfunction "1_1") (pintype "bidirectional"))
      (node (ref "J2") (pin "4") (pinfunction "4_4") (pintype "bidirectional"))
      (node (ref "J2") (pin "6") (pinfunction "6_6") (pintype "bidirectional"))
      (node (ref "J2") (pin "8") (pinfunction "8_8") (pintype "bidirectional"))
    )
    (net (code "121") (name "/TEC1-") (class "Default")
      (node (ref "B6") (pin "1") (pinfunction "1_1") (pintype "bidirectional"))
      (node (ref "J2") (pin "5") (pinfunction "5_5") (pintype "bidirectional"))
      (node (ref "J2") (pin "7") (pinfunction "7_7") (pintype "bidirectional"))
      (node (ref "J2") (pin "9") (pinfunction "9_9") (pintype "bidirectional"))
    )
    (net (code "124") (name "GND") (class "Default")
      (node (ref "C11") (pin "2") (pinfunction "2_2") (pintype "passive"))
      (node (ref "C15") (pin "2") (pinfunction "2_2") (pintype "passive"))
      (node (ref "C68") (pin "1") (pinfunction "1_1") (pintype "passive"))
      (node (ref "C71") (pin "1") (pinfunction "1_1") (pintype "passive"))
      (node (ref "C95") (pin "1") (pinfunction "1_1") (pintype "passive"))
      (node (ref "C96") (pin "1") (pinfunction "1_1") (pintype "passive"))
      (node (ref "CLIP28") (pin "1") (pinfunction "1_1") (pintype "passive"))
      (node (ref "CLIP29") (pin "1") (pinfunction "1_1") (pintype "passive"))
      (node (ref "CLIP30") (pin "1") (pinfunction "1_1") (pintype "passive"))
      (node (ref "CLIP31") (pin "1") (pinfunction "1_1") (pintype "passive"))
      (node (ref "CLIP32") (pin "1") (pinfunction "1_1") (pintype "passive"))
      (node (ref "CLIP33") (pin "1") (pinfunction "1_1") (pintype "passive"))
      (node (ref "CLIP34") (pin "1") (pinfunction "1_1") (pintype "passive"))
      (node (ref "CLIP37") (pin "1") (pinfunction "1_1") (pintype "passive"))
      (node (ref "CLIP38") (pin "1") (pinfunction "1_1") (pintype "passive"))
      (node (ref "CLIP39") (pin "1") (pinfunction "1_1") (pintype "passive"))
      (node (ref "CLIP40") (pin "1") (pinfunction "1_1") (pintype "passive"))
      (node (ref "CLIP41") (pin "1") (pinfunction "1_1") (pintype "passive"))
      (node (ref "CLIP42") (pin "1") (pinfunction "1_1") (pintype "passive"))
      (node (ref "CLIP43") (pin "1") (pinfunction "1_1") (pintype "passive"))
      (node (ref "CLIP44") (pin "1") (pinfunction "1_1") (pintype "passive"))
      (node (ref "CLIP45") (pin "1") (pinfunction "1_1") (pintype "passive"))
      (node (ref "CLIP46") (pin "1") (pinfunction "1_1") (pintype "passive"))
      (node (ref "CLIP47") (pin "1") (pinfunction "1_1") (pintype "passive"))
      (node (ref "IC19") (pin "1") (pinfunction "VSS_1") (pintype "power_in"))
      (node (ref "IC23") (pin "13") (pinfunction "~{OE}_13") (pintype "input"))
      (node (ref "IC23") (pin "8") (pinfunction "GND_8") (pintype "power_in"))
      (node (ref "J1") (pin "17") (pinfunction "17_17") (pintype "bidirectional"))
      (node (ref "J1") (pin "51") (pinfunction "51_51") (pintype "bidirectional"))
      (node (ref "J1") (pin "69") (pinfunction "69_69") (pintype "bidirectional"))
      (node (ref "J1") (pin "70") (pinfunction "70_70") (pintype "bidirectional"))
      (node (ref "J2") (pin "3") (pinfunction "3_3") (pintype "bidirectional"))
      (node (ref "J3") (pin "12") (pinfunction "12_12") (pintype "bidirectional"))
      (node (ref "J3") (pin "15") (pinfunction "15_15") (pintype "bidirectional"))
      (node (ref "J3") (pin "18") (pinfunction "18_18") (pintype "bidirectional"))
      (node (ref "J3") (pin "21") (pinfunction "21_21") (pintype "bidirectional"))
      (node (ref "J3") (pin "24") (pinfunction "24_24") (pintype "bidirectional"))
      (node (ref "J3") (pin "3") (pinfunction "3_3") (pintype "bidirectional"))
      (node (ref "J3") (pin "6") (pinfunction "6_6") (pintype "bidirectional"))
      (node (ref "J3") (pin "9") (pinfunction "9_9") (pintype "bidirectional"))
      (node (ref "J4") (pin "12") (pinfunction "12_12") (pintype "bidirectional"))
      (node (ref "J4") (pin "15") (pinfunction "15_15") (pintype "bidirectional"))
      (node (ref "J4") (pin "18") (pinfunction "18_18") (pintype "bidirectional"))
      (node (ref "J4") (pin "21") (pinfunction "21_21") (pintype "bidirectional"))
      (node (ref "J4") (pin "24") (pinfunction "24_24") (pintype "bidirectional"))
      (node (ref "J4") (pin "3") (pinfunction "3_3") (pintype "bidirectional"))
      (node (ref "J4") (pin "6") (pinfunction "6_6") (pintype "bidirectional"))
      (node (ref "J4") (pin "9") (pinfunction "9_9") (pintype "bidirectional"))
      (node (ref "J5") (pin "12") (pinfunction "12_12") (pintype "bidirectional"))
      (node (ref "J5") (pin "15") (pinfunction "15_15") (pintype "bidirectional"))
      (node (ref "J5") (pin "18") (pinfunction "18_18") (pintype "bidirectional"))
      (node (ref "J5") (pin "21") (pinfunction "21_21") (pintype "bidirectional"))
      (node (ref "J5") (pin "24") (pinfunction "24_24") (pintype "bidirectional"))
      (node (ref "J5") (pin "3") (pinfunction "3_3") (pintype "bidirectional"))
      (node (ref "J5") (pin "6") (pinfunction "6_6") (pintype "bidirectional"))
      (node (ref "J5") (pin "9") (pinfunction "9_9") (pintype "bidirectional"))
      (node (ref "J7") (pin "12") (pinfunction "12_12") (pintype "bidirectional"))
      (node (ref "J7") (pin "15") (pinfunction "15_15") (pintype "bidirectional"))
      (node (ref "J7") (pin "18") (pinfunction "18_18") (pintype "bidirectional"))
      (node (ref "J7") (pin "21") (pinfunction "21_21") (pintype "bidirectional"))
      (node (ref "J7") (pin "24") (pinfunction "24_24") (pintype "bidirectional"))
      (node (ref "J7") (pin "3") (pinfunction "3_3") (pintype "bidirectional"))
      (node (ref "J7") (pin "6") (pinfunction "6_6") (pintype "bidirectional"))
      (node (ref "J7") (pin "9") (pinfunction "9_9") (pintype "bidirectional"))
      (node (ref "LD4") (pin "1") (pinfunction "C_1") (pintype "passive"))
      (node (ref "LD4") (pin "3") (pinfunction "C_3") (pintype "passive"))
      (node (ref "LD4") (pin "5") (pinfunction "C_5") (pintype "passive"))
      (node (ref "LD4") (pin "7") (pinfunction "C_7") (pintype "passive"))
      (node (ref "LD5") (pin "1") (pinfunction "C_1") (pintype "passive"))
      (node (ref "LD5") (pin "3") (pinfunction "C_3") (pintype "passive"))
      (node (ref "LD5") (pin "5") (pinfunction "C_5") (pintype "passive"))
      (node (ref "LD5") (pin "7") (pinfunction "C_7") (pintype "passive"))
      (node (ref "R15") (pin "1") (pinfunction "1_1") (pintype "passive"))
      (node (ref "R28") (pin "1") (pinfunction "1_1") (pintype "passive"))
      (node (ref "R29") (pin "1") (pinfunction "1_1") (pintype "passive"))
    )
    (net (code "125") (name "N12V0A") (class "Default")
      (node (ref "R10") (pin "1") (pinfunction "1_1") (pintype "passive"))
      (node (ref "R10") (pin "2") (pinfunction "2_2") (pintype "passive"))
      (node (ref "R12") (pin "1") (pinfunction "1_1") (pintype "passive"))
      (node (ref "R12") (pin "2") (pinfunction "2_2") (pintype "passive"))
      (node (ref "R8") (pin "1") (pinfunction "1_1") (pintype "passive"))
      (node (ref "R8") (pin "2") (pinfunction "2_2") (pintype "passive"))
      (node (ref "R9") (pin "1") (pinfunction "1_1") (pintype "passive"))
      (node (ref "R9") (pin "2") (pinfunction "2_2") (pintype "passive"))
    )
    (net (code "126") (name "N13V0_SCSI") (class "Default")
      (node (ref "J1") (pin "52") (pinfunction "52_52") (pintype "bidirectional"))
      (node (ref "J3") (pin "26") (pinfunction "26_26") (pintype "bidirectional"))
      (node (ref "J4") (pin "26") (pinfunction "26_26") (pintype "bidirectional"))
      (node (ref "J5") (pin "26") (pinfunction "26_26") (pintype "bidirectional"))
      (node (ref "J7") (pin "26") (pinfunction "26_26") (pintype "bidirectional"))
    )
    (net (code "127") (name "Net-(B1-Pad1)") (class "Default")
      (node (ref "B1") (pin "1") (pinfunction "1_1") (pintype "bidirectional"))
      (node (ref "C11") (pin "1") (pinfunction "1_1") (pintype "passive"))
      (node (ref "R28") (pin "2") (pinfunction "2_2") (pintype "passive"))
    )
    (net (code "128") (name "Net-(B7-Pad1)") (class "Default")
      (node (ref "B7") (pin "1") (pinfunction "1_1") (pintype "bidirectional"))
      (node (ref "C15") (pin "1") (pinfunction "1_1") (pintype "passive"))
      (node (ref "R29") (pin "2") (pinfunction "2_2") (pintype "passive"))
    )
    (net (code "129") (name "Net-(C68-Pad2)") (class "Default")
      (node (ref "C68") (pin "2") (pinfunction "2_2") (pintype "passive"))
      (node (ref "R117") (pin "1") (pinfunction "1_1") (pintype "passive"))
    )
    (net (code "130") (name "Net-(C71-Pad2)") (class "Default")
      (node (ref "C71") (pin "2") (pinfunction "2_2") (pintype "passive"))
      (node (ref "R118") (pin "1") (pinfunction "1_1") (pintype "passive"))
    )
    (net (code "131") (name "Net-(C95-Pad2)") (class "Default")
      (node (ref "C95") (pin "2") (pinfunction "2_2") (pintype "passive"))
      (node (ref "R116") (pin "1") (pinfunction "1_1") (pintype "passive"))
    )
    (net (code "132") (name "Net-(LD4A-A)") (class "Default")
      (node (ref "LD4") (pin "2") (pinfunction "A_2") (pintype "passive"))
      (node (ref "R113") (pin "2") (pinfunction "2_2") (pintype "passive"))
    )
    (net (code "133") (name "Net-(LD4B-A)") (class "Default")
      (node (ref "LD4") (pin "4") (pinfunction "A_4") (pintype "passive"))
      (node (ref "R114") (pin "2") (pinfunction "2_2") (pintype "passive"))
    )
    (net (code "134") (name "Net-(LD4C-A)") (class "Default")
      (node (ref "LD4") (pin "6") (pinfunction "A_6") (pintype "passive"))
      (node (ref "R115") (pin "2") (pinfunction "2_2") (pintype "passive"))
    )
    (net (code "135") (name "Net-(LD4D-A)") (class "Default")
      (node (ref "LD4") (pin "8") (pinfunction "A_8") (pintype "passive"))
      (node (ref "R119") (pin "2") (pinfunction "2_2") (pintype "passive"))
    )
    (net (code "136") (name "Net-(LD5A-A)") (class "Default")
      (node (ref "LD5") (pin "2") (pinfunction "A_2") (pintype "passive"))
      (node (ref "R120") (pin "2") (pinfunction "2_2") (pintype "passive"))
    )
    (net (code "137") (name "Net-(LD5B-A)") (class "Default")
      (node (ref "LD5") (pin "4") (pinfunction "A_4") (pintype "passive"))
      (node (ref "R121") (pin "2") (pinfunction "2_2") (pintype "passive"))
    )
    (net (code "138") (name "Net-(LD5C-A)") (class "Default")
      (node (ref "LD5") (pin "6") (pinfunction "A_6") (pintype "passive"))
      (node (ref "R122") (pin "2") (pinfunction "2_2") (pintype "passive"))
    )
    (net (code "139") (name "Net-(LD5D-A)") (class "Default")
      (node (ref "LD5") (pin "8") (pinfunction "A_8") (pintype "passive"))
      (node (ref "R123") (pin "2") (pinfunction "2_2") (pintype "passive"))
    )
    (net (code "140") (name "P3V3") (class "Default")
      (node (ref "C96") (pin "2") (pinfunction "2_2") (pintype "passive"))
      (node (ref "IC19") (pin "3") (pinfunction "~{MR}_3") (pintype "input"))
      (node (ref "IC19") (pin "4") (pinfunction "VCC_4") (pintype "power_in"))
      (node (ref "IC23") (pin "10") (pinfunction "~{SRCLR}_10") (pintype "input"))
      (node (ref "IC23") (pin "16") (pinfunction "VCC_16") (pintype "power_in"))
    )
    (net (code "141") (name "P12V0") (class "Default")
      (node (ref "J2") (pin "10") (pinfunction "10_10") (pintype "bidirectional"))
    )
    (net (code "142") (name "P13V0_SCSI") (class "Default")
      (node (ref "J1") (pin "18") (pinfunction "18_18") (pintype "bidirectional"))
      (node (ref "J3") (pin "25") (pinfunction "25_25") (pintype "bidirectional"))
      (node (ref "J4") (pin "25") (pinfunction "25_25") (pintype "bidirectional"))
      (node (ref "J5") (pin "25") (pinfunction "25_25") (pintype "bidirectional"))
      (node (ref "J7") (pin "25") (pinfunction "25_25") (pintype "bidirectional"))
    )
    (net (code "143") (name "unconnected-(B2-Pad1)") (class "Default")
      (node (ref "B2") (pin "1") (pinfunction "1_1") (pintype "bidirectional"))
    )
    (net (code "144") (name "unconnected-(B3-Pad1)") (class "Default")
      (node (ref "B3") (pin "1") (pinfunction "1_1") (pintype "bidirectional"))
    )
    (net (code "145") (name "unconnected-(B4-Pad1)") (class "Default")
      (node (ref "B4") (pin "1") (pinfunction "1_1") (pintype "bidirectional"))
    )
    (net (code "146") (name "unconnected-(B8-Pad1)") (class "Default")
      (node (ref "B8") (pin "1") (pinfunction "1_1") (pintype "bidirectional"))
    )
    (net (code "147") (name "unconnected-(B9-Pad1)") (class "Default")
      (node (ref "B9") (pin "1") (pinfunction "1_1") (pintype "bidirectional"))
    )
    (net (code "148") (name "unconnected-(B10-Pad1)") (class "Default")
      (node (ref "B10") (pin "1") (pinfunction "1_1") (pintype "bidirectional"))
    )
    (net (code "149") (name "unconnected-(IC23-QH'-Pad9)") (class "Default")
      (node (ref "IC23") (pin "9") (pinfunction "QH'_9") (pintype "output"))
    )
  )
)
